# DRAMCarrier_250425.net
KiCad netlist of a schematic drawn in EAGLE
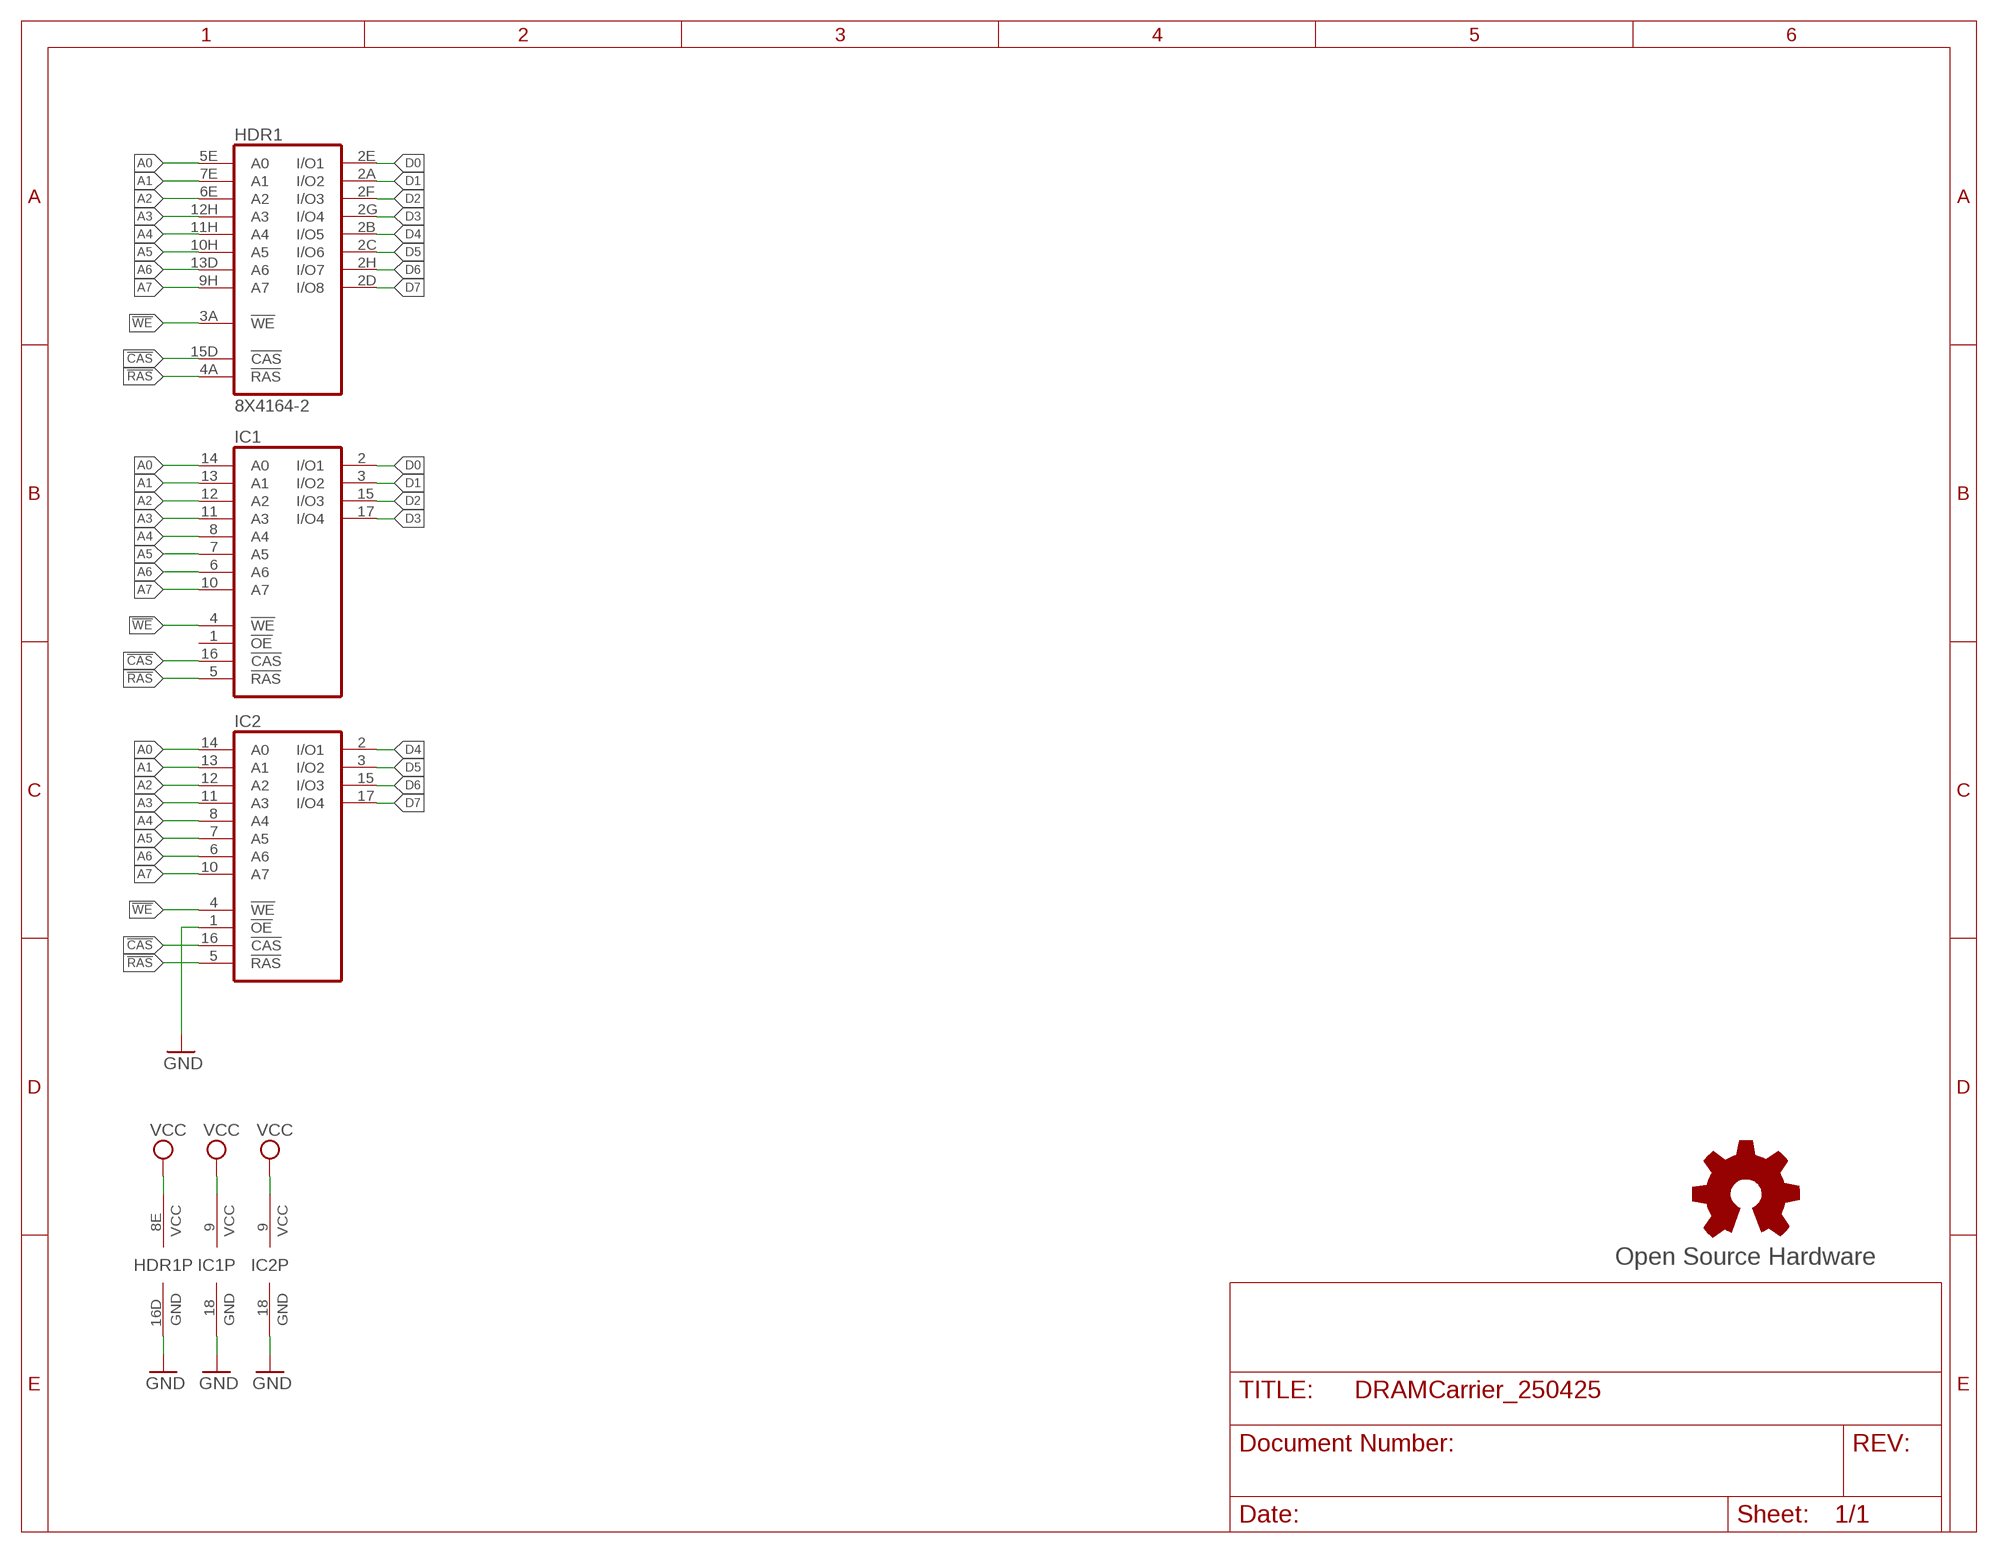
[diagram p0: schematic, sheet 1]

(export (version "E")
  (design (tool "Eeschema 10.0.6"))
  (components
    (comp (ref "GOLD_ORB_SM1")
      (value "Open Source Hardware")
      (footprint "eagle-import:OSHW_8MM")
      (libsource (lib "eagle-import") (part "OSHWLOGOLOGO8MM"))
    )
    (comp (ref "HDR1")
      (value "8X4164-2")
      (footprint "eagle-import:8XDIL16_REV2")
      (libsource (lib "eagle-import") (part "8X4164-2"))
    )
    (comp (ref "IC1")
      (value "41464C")
      (footprint "eagle-import:DIL18")
      (libsource (lib "eagle-import") (part "41464C"))
    )
    (comp (ref "IC2")
      (value "41464C")
      (footprint "eagle-import:DIL18")
      (libsource (lib "eagle-import") (part "41464C"))
    )
  )
  (nets
    (net (code "1") (name "/~{CAS}") (class "Default")
      (node (ref "HDR1") (pin "15D") (pinfunction "~{CAS}_15D") (pintype "input"))
      (node (ref "IC1") (pin "16") (pinfunction "~{CAS}_16") (pintype "input"))
      (node (ref "IC2") (pin "16") (pinfunction "~{CAS}_16") (pintype "input"))
    )
    (net (code "2") (name "/~{RAS}") (class "Default")
      (node (ref "HDR1") (pin "4A") (pinfunction "~{RAS}_4A") (pintype "input"))
      (node (ref "IC1") (pin "5") (pinfunction "~{RAS}_5") (pintype "input"))
      (node (ref "IC2") (pin "5") (pinfunction "~{RAS}_5") (pintype "input"))
    )
    (net (code "3") (name "/~{WE}") (class "Default")
      (node (ref "HDR1") (pin "3A") (pinfunction "~{WE}_3A") (pintype "input"))
      (node (ref "IC1") (pin "4") (pinfunction "~{WE}_4") (pintype "input"))
      (node (ref "IC2") (pin "4") (pinfunction "~{WE}_4") (pintype "input"))
    )
    (net (code "4") (name "A0") (class "Default")
      (node (ref "HDR1") (pin "5E") (pinfunction "A0_5E") (pintype "input"))
      (node (ref "IC1") (pin "14") (pinfunction "A0_14") (pintype "input"))
      (node (ref "IC2") (pin "14") (pinfunction "A0_14") (pintype "input"))
    )
    (net (code "5") (name "A1") (class "Default")
      (node (ref "HDR1") (pin "7E") (pinfunction "A1_7E") (pintype "input"))
      (node (ref "IC1") (pin "13") (pinfunction "A1_13") (pintype "input"))
      (node (ref "IC2") (pin "13") (pinfunction "A1_13") (pintype "input"))
    )
    (net (code "6") (name "A2") (class "Default")
      (node (ref "HDR1") (pin "6E") (pinfunction "A2_6E") (pintype "input"))
      (node (ref "IC1") (pin "12") (pinfunction "A2_12") (pintype "input"))
      (node (ref "IC2") (pin "12") (pinfunction "A2_12") (pintype "input"))
    )
    (net (code "7") (name "A3") (class "Default")
      (node (ref "HDR1") (pin "12H") (pinfunction "A3_12H") (pintype "input"))
      (node (ref "IC1") (pin "11") (pinfunction "A3_11") (pintype "input"))
      (node (ref "IC2") (pin "11") (pinfunction "A3_11") (pintype "input"))
    )
    (net (code "8") (name "A4") (class "Default")
      (node (ref "HDR1") (pin "11H") (pinfunction "A4_11H") (pintype "input"))
      (node (ref "IC1") (pin "8") (pinfunction "A4_8") (pintype "input"))
      (node (ref "IC2") (pin "8") (pinfunction "A4_8") (pintype "input"))
    )
    (net (code "9") (name "A5") (class "Default")
      (node (ref "HDR1") (pin "10H") (pinfunction "A5_10H") (pintype "input"))
      (node (ref "IC1") (pin "7") (pinfunction "A5_7") (pintype "input"))
      (node (ref "IC2") (pin "7") (pinfunction "A5_7") (pintype "input"))
    )
    (net (code "10") (name "A6") (class "Default")
      (node (ref "HDR1") (pin "13D") (pinfunction "A6_13D") (pintype "input"))
      (node (ref "IC1") (pin "6") (pinfunction "A6_6") (pintype "input"))
      (node (ref "IC2") (pin "6") (pinfunction "A6_6") (pintype "input"))
    )
    (net (code "11") (name "A7") (class "Default")
      (node (ref "HDR1") (pin "9H") (pinfunction "A7_9H") (pintype "input"))
      (node (ref "IC1") (pin "10") (pinfunction "A7_10") (pintype "input"))
      (node (ref "IC2") (pin "10") (pinfunction "A7_10") (pintype "input"))
    )
    (net (code "12") (name "D0") (class "Default")
      (node (ref "HDR1") (pin "2E") (pinfunction "I/O1_2E") (pintype "bidirectional"))
      (node (ref "IC1") (pin "2") (pinfunction "I/O1_2") (pintype "bidirectional"))
    )
    (net (code "13") (name "D1") (class "Default")
      (node (ref "HDR1") (pin "2A") (pinfunction "I/O2_2A") (pintype "bidirectional"))
      (node (ref "IC1") (pin "3") (pinfunction "I/O2_3") (pintype "bidirectional"))
    )
    (net (code "14") (name "D2") (class "Default")
      (node (ref "HDR1") (pin "2F") (pinfunction "I/O3_2F") (pintype "bidirectional"))
      (node (ref "IC1") (pin "15") (pinfunction "I/O3_15") (pintype "bidirectional"))
    )
    (net (code "15") (name "D3") (class "Default")
      (node (ref "HDR1") (pin "2G") (pinfunction "I/O4_2G") (pintype "bidirectional"))
      (node (ref "IC1") (pin "17") (pinfunction "I/O4_17") (pintype "bidirectional"))
    )
    (net (code "16") (name "D4") (class "Default")
      (node (ref "HDR1") (pin "2B") (pinfunction "I/O5_2B") (pintype "bidirectional"))
      (node (ref "IC2") (pin "2") (pinfunction "I/O1_2") (pintype "bidirectional"))
    )
    (net (code "17") (name "D5") (class "Default")
      (node (ref "HDR1") (pin "2C") (pinfunction "I/O6_2C") (pintype "bidirectional"))
      (node (ref "IC2") (pin "3") (pinfunction "I/O2_3") (pintype "bidirectional"))
    )
    (net (code "18") (name "D6") (class "Default")
      (node (ref "HDR1") (pin "2H") (pinfunction "I/O7_2H") (pintype "bidirectional"))
      (node (ref "IC2") (pin "15") (pinfunction "I/O3_15") (pintype "bidirectional"))
    )
    (net (code "19") (name "D7") (class "Default")
      (node (ref "HDR1") (pin "2D") (pinfunction "I/O8_2D") (pintype "bidirectional"))
      (node (ref "IC2") (pin "17") (pinfunction "I/O4_17") (pintype "bidirectional"))
    )
    (net (code "20") (name "GND") (class "Default")
      (node (ref "HDR1") (pin "16D") (pinfunction "GND_16D") (pintype "power_in"))
      (node (ref "IC1") (pin "18") (pinfunction "GND_18") (pintype "power_in"))
      (node (ref "IC2") (pin "1") (pinfunction "~{OE}_1") (pintype "input"))
      (node (ref "IC2") (pin "18") (pinfunction "GND_18") (pintype "power_in"))
    )
    (net (code "21") (name "VCC") (class "Default")
      (node (ref "HDR1") (pin "8E") (pinfunction "VCC_8E") (pintype "power_in"))
      (node (ref "IC1") (pin "9") (pinfunction "VCC_9") (pintype "power_in"))
      (node (ref "IC2") (pin "9") (pinfunction "VCC_9") (pintype "power_in"))
    )
    (net (code "22") (name "unconnected-(IC1A-~{OE}-Pad1)") (class "Default")
      (node (ref "IC1") (pin "1") (pinfunction "~{OE}_1") (pintype "input"))
    )
  )
)
